# STM32H743_Breakout_V2_TOP.net
KiCad netlist of a schematic drawn in Altium Designer
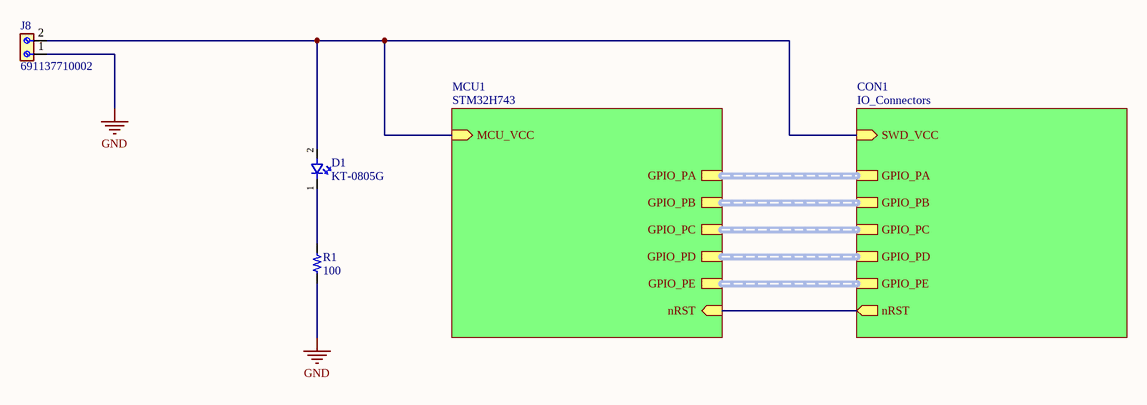
[diagram p0: STM32H743_Breakout_V2_TOP.SchDoc]

(export (version "E")
  (design (tool "Eeschema 10.0.6"))
  (components
    (comp (ref "D1")
      (value "KT-0805G")
      (footprint "HubeiKENTO_0805")
      (description "Green 520nm LED 2.8V 0805")
      (libsource (lib "Project Rapid - Bruin Space") (part "LED-2T"))
    )
    (comp (ref "J8")
      (value "691137710002")
      (footprint "691137710002")
      (description "2 Position Wire to Board Terminal Block Horizontal with Board 0.197 (5.00mm) Through Hole")
      (fields (field (name "MF") "Wurth Electronics"))
      (libsource (lib "Project Rapid - Bruin Space") (part "691137710002"))
    )
    (comp (ref "R1")
      (value "R 0603 100 1% 0.100W 200PPM")
      (footprint "R-0603")
      (description "SMD Resistor, Thick Film")
      (fields (field (name "RESISTANCE") "100") (field (name "TOLERANCE") "1%"))
      (libsource (lib "Project Rapid - Bruin Space") (part "Resistor"))
    )
  )
  (nets
    (net (code "6") (name "/MCU_VCC") (class "Default")
      (node (ref "D1") (pin "2") (pinfunction "2_2") (pintype "passive"))
      (node (ref "J8") (pin "2") (pinfunction "2_2") (pintype "passive"))
    )
    (net (code "8") (name "GND") (class "Default")
      (node (ref "J8") (pin "1") (pinfunction "1_1") (pintype "passive"))
      (node (ref "R1") (pin "1") (pinfunction "1_1") (pintype "passive"))
    )
    (net (code "9") (name "Net-(D1-Pad1)") (class "Default")
      (node (ref "D1") (pin "1") (pinfunction "1_1") (pintype "passive"))
      (node (ref "R1") (pin "2") (pinfunction "2_2") (pintype "passive"))
    )
  )
)
